# First_Schema.net
KiCad netlist of a schematic drawn in EAGLE
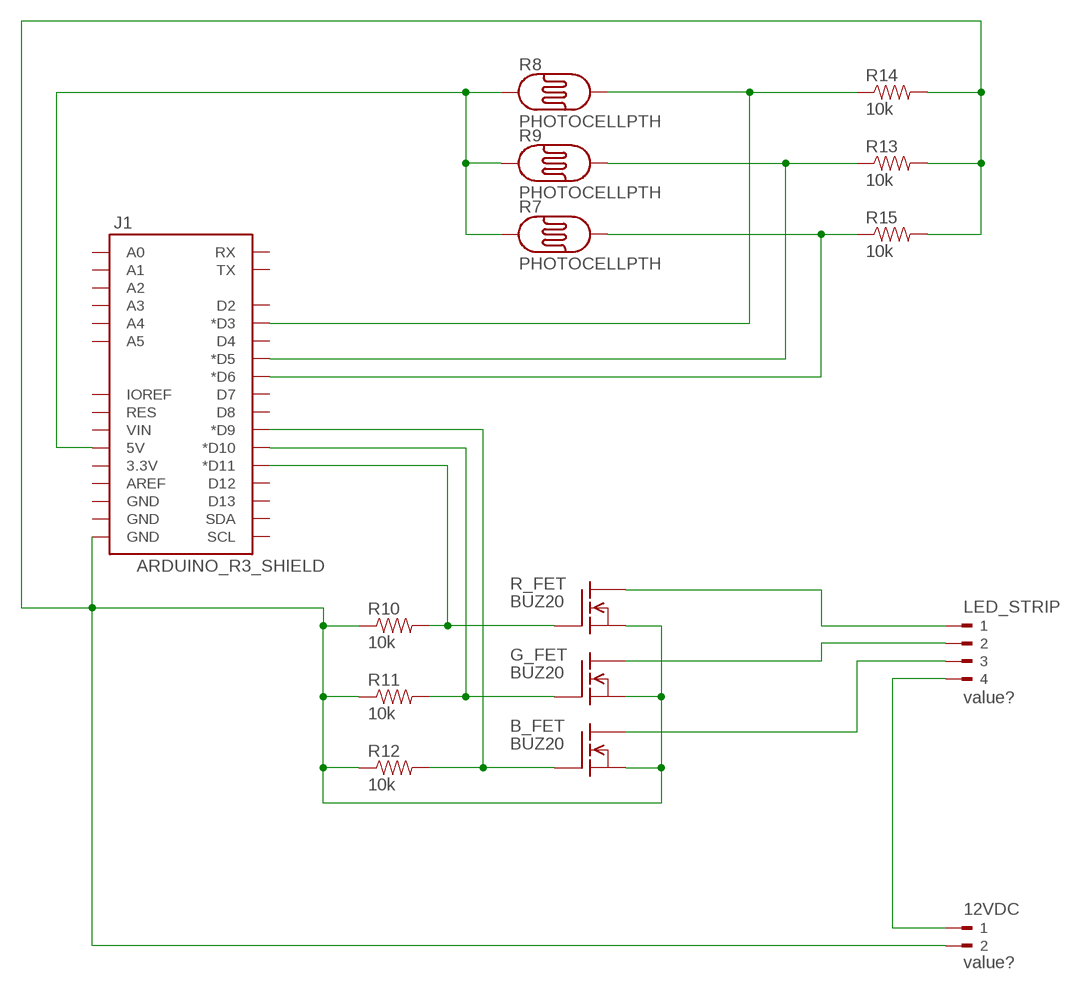
[diagram p0: schematic, sheet 1]

(export (version "E")
  (design (tool "Eeschema 10.0.6"))
  (components
    (comp (ref "12VDC")
      (value "value?")
      (footprint "eagle-import:180-2")
      (libsource (lib "eagle-import") (part "180-2"))
    )
    (comp (ref "B_FET")
      (value "BUZ20")
      (footprint "eagle-import:TO220")
      (libsource (lib "eagle-import") (part "BUZ20"))
    )
    (comp (ref "G_FET")
      (value "BUZ20")
      (footprint "eagle-import:TO220")
      (libsource (lib "eagle-import") (part "BUZ20"))
    )
    (comp (ref "J1")
      (value "ARDUINO_R3_SHIELD")
      (footprint "eagle-import:UNO_R3_SHIELD")
      (libsource (lib "eagle-import") (part "ARDUINO_R3_SHIELD"))
    )
    (comp (ref "LED_STRIP")
      (value "value?")
      (footprint "eagle-import:180-4")
      (libsource (lib "eagle-import") (part "180-4"))
    )
    (comp (ref "R7")
      (value "PHOTOCELLPTH")
      (footprint "eagle-import:PHOTOCELL")
      (libsource (lib "eagle-import") (part "PHOTOCELLPTH"))
    )
    (comp (ref "R8")
      (value "PHOTOCELLPTH")
      (footprint "eagle-import:PHOTOCELL")
      (libsource (lib "eagle-import") (part "PHOTOCELLPTH"))
    )
    (comp (ref "R9")
      (value "PHOTOCELLPTH")
      (footprint "eagle-import:PHOTOCELL")
      (libsource (lib "eagle-import") (part "PHOTOCELLPTH"))
    )
    (comp (ref "R10")
      (value "10k")
      (footprint "eagle-import:AXIAL-0.4")
      (libsource (lib "eagle-import") (part "RESISTORPTH-1/4W"))
    )
    (comp (ref "R11")
      (value "10k")
      (footprint "eagle-import:AXIAL-0.4")
      (libsource (lib "eagle-import") (part "RESISTORPTH-1/4W"))
    )
    (comp (ref "R12")
      (value "10k")
      (footprint "eagle-import:AXIAL-0.4")
      (libsource (lib "eagle-import") (part "RESISTORPTH-1/4W"))
    )
    (comp (ref "R13")
      (value "10k")
      (footprint "eagle-import:AXIAL-0.4")
      (libsource (lib "eagle-import") (part "RESISTORPTH-1/4W"))
    )
    (comp (ref "R14")
      (value "10k")
      (footprint "eagle-import:AXIAL-0.4")
      (libsource (lib "eagle-import") (part "RESISTORPTH-1/4W"))
    )
    (comp (ref "R15")
      (value "10k")
      (footprint "eagle-import:AXIAL-0.4")
      (libsource (lib "eagle-import") (part "RESISTORPTH-1/4W"))
    )
    (comp (ref "R_FET")
      (value "BUZ20")
      (footprint "eagle-import:TO220")
      (libsource (lib "eagle-import") (part "BUZ20"))
    )
  )
  (nets
    (net (code "1") (name "Net-(12VDC-Pad1)") (class "Default")
      (node (ref "12VDC") (pin "1") (pinfunction "1_1") (pintype "passive"))
      (node (ref "LED_STRIP") (pin "4") (pinfunction "4_4") (pintype "passive"))
    )
    (net (code "2") (name "Net-(B_FET-D)") (class "Default")
      (node (ref "B_FET") (pin "2") (pinfunction "D_2") (pintype "passive"))
      (node (ref "LED_STRIP") (pin "3") (pinfunction "3_3") (pintype "passive"))
    )
    (net (code "3") (name "Net-(B_FET-G)") (class "Default")
      (node (ref "B_FET") (pin "1") (pinfunction "G_1") (pintype "passive"))
      (node (ref "J1") (pin "D9") (pinfunction "*D9_D9") (pintype "bidirectional"))
      (node (ref "R12") (pin "P$2") (pinfunction "2_P$2") (pintype "passive"))
    )
    (net (code "4") (name "Net-(B_FET-S)") (class "Default")
      (node (ref "12VDC") (pin "2") (pinfunction "2_2") (pintype "passive"))
      (node (ref "B_FET") (pin "3") (pinfunction "S_3") (pintype "passive"))
      (node (ref "G_FET") (pin "3") (pinfunction "S_3") (pintype "passive"))
      (node (ref "J1") (pin "GND@0") (pinfunction "GND_GND@0") (pintype "bidirectional"))
      (node (ref "R10") (pin "P$1") (pinfunction "1_P$1") (pintype "passive"))
      (node (ref "R11") (pin "P$1") (pinfunction "1_P$1") (pintype "passive"))
      (node (ref "R12") (pin "P$1") (pinfunction "1_P$1") (pintype "passive"))
      (node (ref "R13") (pin "P$2") (pinfunction "2_P$2") (pintype "passive"))
      (node (ref "R14") (pin "P$2") (pinfunction "2_P$2") (pintype "passive"))
      (node (ref "R15") (pin "P$2") (pinfunction "2_P$2") (pintype "passive"))
      (node (ref "R_FET") (pin "3") (pinfunction "S_3") (pintype "passive"))
    )
    (net (code "5") (name "Net-(G_FET-D)") (class "Default")
      (node (ref "G_FET") (pin "2") (pinfunction "D_2") (pintype "passive"))
      (node (ref "LED_STRIP") (pin "2") (pinfunction "2_2") (pintype "passive"))
    )
    (net (code "6") (name "Net-(G_FET-G)") (class "Default")
      (node (ref "G_FET") (pin "1") (pinfunction "G_1") (pintype "passive"))
      (node (ref "J1") (pin "D10") (pinfunction "*D10_D10") (pintype "bidirectional"))
      (node (ref "R11") (pin "P$2") (pinfunction "2_P$2") (pintype "passive"))
    )
    (net (code "7") (name "Net-(J1-*D3)") (class "Default")
      (node (ref "J1") (pin "D3") (pinfunction "*D3_D3") (pintype "bidirectional"))
      (node (ref "R14") (pin "P$1") (pinfunction "1_P$1") (pintype "passive"))
      (node (ref "R8") (pin "2") (pinfunction "P$2_2") (pintype "bidirectional"))
    )
    (net (code "8") (name "Net-(J1-*D5)") (class "Default")
      (node (ref "J1") (pin "D5") (pinfunction "*D5_D5") (pintype "bidirectional"))
      (node (ref "R13") (pin "P$1") (pinfunction "1_P$1") (pintype "passive"))
      (node (ref "R9") (pin "2") (pinfunction "P$2_2") (pintype "bidirectional"))
    )
    (net (code "9") (name "Net-(J1-*D6)") (class "Default")
      (node (ref "J1") (pin "D6") (pinfunction "*D6_D6") (pintype "bidirectional"))
      (node (ref "R15") (pin "P$1") (pinfunction "1_P$1") (pintype "passive"))
      (node (ref "R7") (pin "2") (pinfunction "P$2_2") (pintype "bidirectional"))
    )
    (net (code "10") (name "Net-(J1-*D11)") (class "Default")
      (node (ref "J1") (pin "D11") (pinfunction "*D11_D11") (pintype "bidirectional"))
      (node (ref "R10") (pin "P$2") (pinfunction "2_P$2") (pintype "passive"))
      (node (ref "R_FET") (pin "1") (pinfunction "G_1") (pintype "passive"))
    )
    (net (code "11") (name "Net-(R7-P$1)") (class "Default")
      (node (ref "J1") (pin "5V") (pinfunction "5V_5V") (pintype "bidirectional"))
      (node (ref "R7") (pin "1") (pinfunction "P$1_1") (pintype "bidirectional"))
      (node (ref "R8") (pin "1") (pinfunction "P$1_1") (pintype "bidirectional"))
      (node (ref "R9") (pin "1") (pinfunction "P$1_1") (pintype "bidirectional"))
    )
    (net (code "12") (name "Net-(R_FET-D)") (class "Default")
      (node (ref "LED_STRIP") (pin "1") (pinfunction "1_1") (pintype "passive"))
      (node (ref "R_FET") (pin "2") (pinfunction "D_2") (pintype "passive"))
    )
    (net (code "13") (name "unconnected-(J1-GND-PadGND@1)") (class "Default")
      (node (ref "J1") (pin "GND@1") (pinfunction "GND_GND@1") (pintype "bidirectional"))
    )
    (net (code "14") (name "unconnected-(J1-GND-PadGND@2)") (class "Default")
      (node (ref "J1") (pin "GND@2") (pinfunction "GND_GND@2") (pintype "bidirectional"))
    )
    (net (code "15") (name "unconnected-(J1-Pad3.3V)") (class "Default")
      (node (ref "J1") (pin "3.3V") (pinfunction "3.3V_3.3V") (pintype "bidirectional"))
    )
    (net (code "16") (name "unconnected-(J1-PadA0)") (class "Default")
      (node (ref "J1") (pin "A0") (pinfunction "A0_A0") (pintype "bidirectional"))
    )
    (net (code "17") (name "unconnected-(J1-PadA1)") (class "Default")
      (node (ref "J1") (pin "A1") (pinfunction "A1_A1") (pintype "bidirectional"))
    )
    (net (code "18") (name "unconnected-(J1-PadA2)") (class "Default")
      (node (ref "J1") (pin "A2") (pinfunction "A2_A2") (pintype "bidirectional"))
    )
    (net (code "19") (name "unconnected-(J1-PadA3)") (class "Default")
      (node (ref "J1") (pin "A3") (pinfunction "A3_A3") (pintype "bidirectional"))
    )
    (net (code "20") (name "unconnected-(J1-PadA4)") (class "Default")
      (node (ref "J1") (pin "A4") (pinfunction "A4_A4") (pintype "bidirectional"))
    )
    (net (code "21") (name "unconnected-(J1-PadA5)") (class "Default")
      (node (ref "J1") (pin "A5") (pinfunction "A5_A5") (pintype "bidirectional"))
    )
    (net (code "22") (name "unconnected-(J1-PadAREF)") (class "Default")
      (node (ref "J1") (pin "AREF") (pinfunction "AREF_AREF") (pintype "bidirectional"))
    )
    (net (code "23") (name "unconnected-(J1-PadD2)") (class "Default")
      (node (ref "J1") (pin "D2") (pinfunction "D2_D2") (pintype "bidirectional"))
    )
    (net (code "24") (name "unconnected-(J1-PadD4)") (class "Default")
      (node (ref "J1") (pin "D4") (pinfunction "D4_D4") (pintype "bidirectional"))
    )
    (net (code "25") (name "unconnected-(J1-PadD7)") (class "Default")
      (node (ref "J1") (pin "D7") (pinfunction "D7_D7") (pintype "bidirectional"))
    )
    (net (code "26") (name "unconnected-(J1-PadD8)") (class "Default")
      (node (ref "J1") (pin "D8") (pinfunction "D8_D8") (pintype "bidirectional"))
    )
    (net (code "27") (name "unconnected-(J1-PadD12)") (class "Default")
      (node (ref "J1") (pin "D12") (pinfunction "D12_D12") (pintype "bidirectional"))
    )
    (net (code "28") (name "unconnected-(J1-PadD13)") (class "Default")
      (node (ref "J1") (pin "D13") (pinfunction "D13_D13") (pintype "bidirectional"))
    )
    (net (code "29") (name "unconnected-(J1-PadIOREF)") (class "Default")
      (node (ref "J1") (pin "IOREF") (pinfunction "IOREF_IOREF") (pintype "bidirectional"))
    )
    (net (code "30") (name "unconnected-(J1-PadRES)") (class "Default")
      (node (ref "J1") (pin "RES") (pinfunction "RES_RES") (pintype "bidirectional"))
    )
    (net (code "31") (name "unconnected-(J1-PadRX)") (class "Default")
      (node (ref "J1") (pin "RX") (pinfunction "RX_RX") (pintype "bidirectional"))
    )
    (net (code "32") (name "unconnected-(J1-PadSCL)") (class "Default")
      (node (ref "J1") (pin "SCL") (pinfunction "SCL_SCL") (pintype "bidirectional"))
    )
    (net (code "33") (name "unconnected-(J1-PadSDA)") (class "Default")
      (node (ref "J1") (pin "SDA") (pinfunction "SDA_SDA") (pintype "bidirectional"))
    )
    (net (code "34") (name "unconnected-(J1-PadTX)") (class "Default")
      (node (ref "J1") (pin "TX") (pinfunction "TX_TX") (pintype "bidirectional"))
    )
    (net (code "35") (name "unconnected-(J1-PadVIN)") (class "Default")
      (node (ref "J1") (pin "VIN") (pinfunction "VIN_VIN") (pintype "bidirectional"))
    )
  )
)
